# ME433_HW3_CPatino_schematic.net
KiCad netlist of a schematic drawn in EAGLE
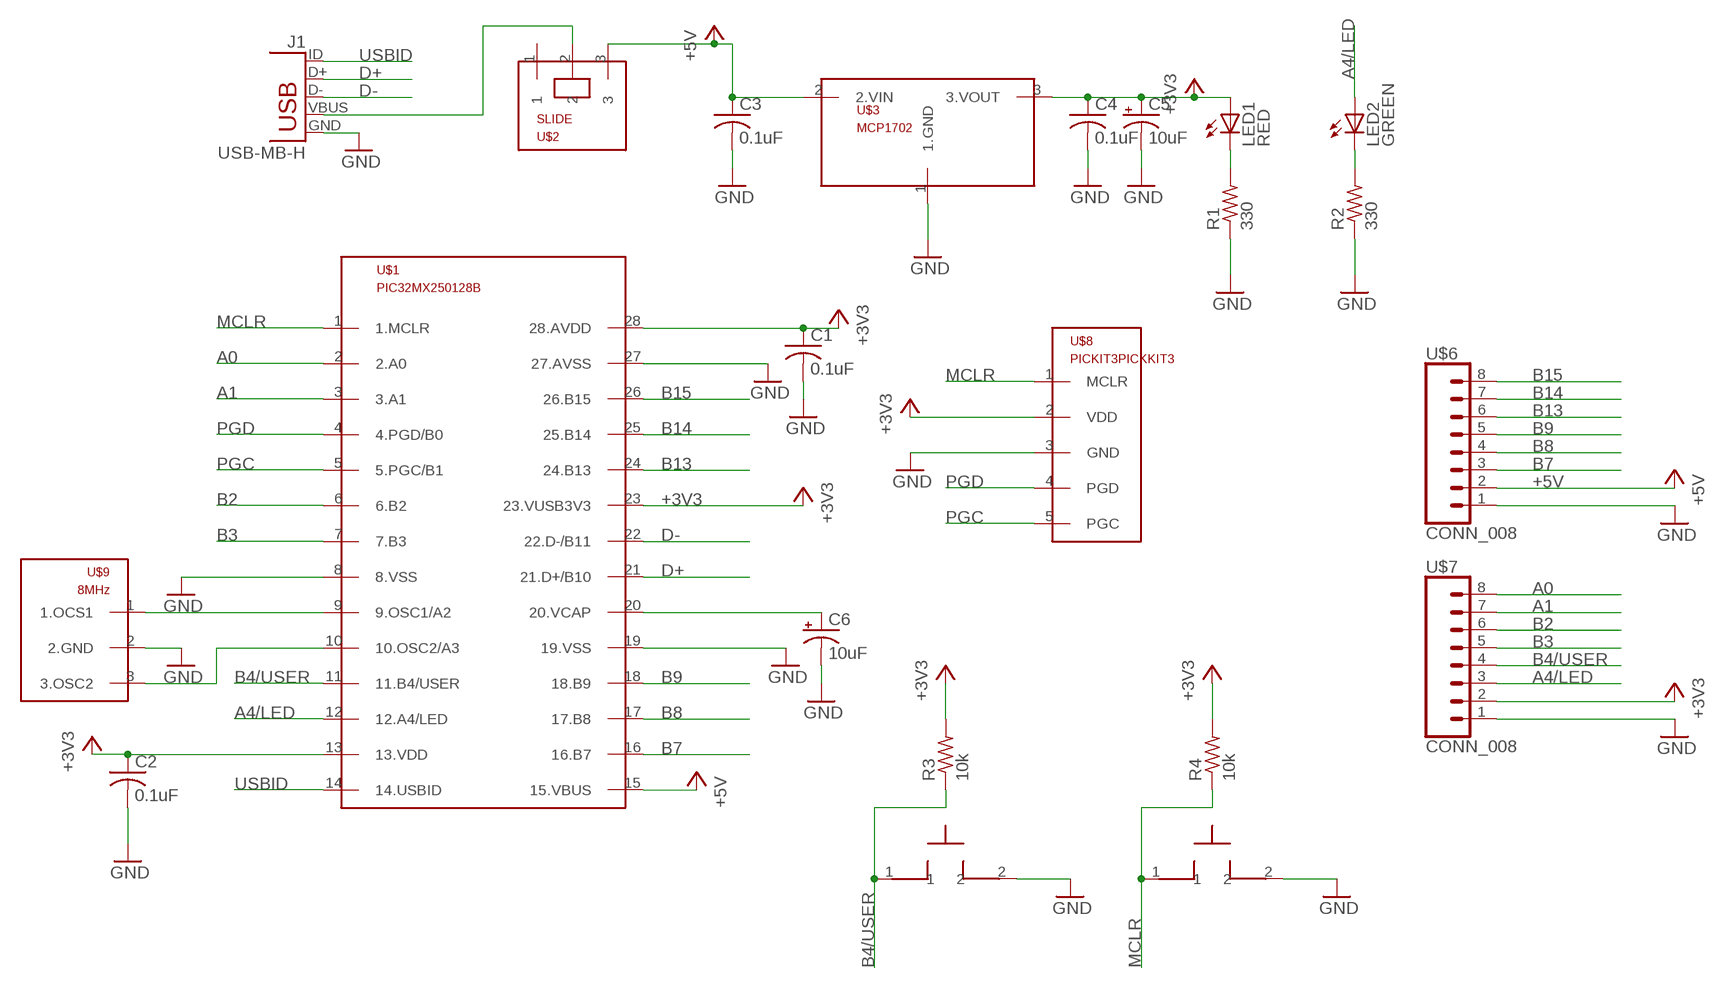
[diagram p0: schematic, sheet 1]

(export (version "E")
  (design (tool "Eeschema 10.0.6"))
  (components
    (comp (ref "C1")
      (value "0.1uF")
      (footprint "eagle-import:C025-025X050")
      (libsource (lib "eagle-import") (part "C-US025-025X050"))
    )
    (comp (ref "C2")
      (value "0.1uF")
      (footprint "eagle-import:C025-025X050")
      (libsource (lib "eagle-import") (part "C-US025-025X050"))
    )
    (comp (ref "C3")
      (value "0.1uF")
      (footprint "eagle-import:C025-025X050")
      (libsource (lib "eagle-import") (part "C-US025-025X050"))
    )
    (comp (ref "C4")
      (value "0.1uF")
      (footprint "eagle-import:C025-025X050")
      (libsource (lib "eagle-import") (part "C-US025-025X050"))
    )
    (comp (ref "C5")
      (value "10uF")
      (footprint "eagle-import:B45181B")
      (libsource (lib "eagle-import") (part "CPOL-USB45181B"))
    )
    (comp (ref "C6")
      (value "10uF")
      (footprint "eagle-import:B45181B")
      (libsource (lib "eagle-import") (part "CPOL-USB45181B"))
    )
    (comp (ref "J1")
      (value "USB-MB-H")
      (footprint "eagle-import:USB-MB-H")
      (libsource (lib "eagle-import") (part "USB-MB-H"))
    )
    (comp (ref "LED1")
      (value "RED")
      (footprint "eagle-import:LED3MM")
      (libsource (lib "eagle-import") (part "LED3MM"))
    )
    (comp (ref "LED2")
      (value "GREEN")
      (footprint "eagle-import:LED3MM")
      (libsource (lib "eagle-import") (part "LED3MM"))
    )
    (comp (ref "R1")
      (value "330")
      (footprint "eagle-import:0207_10")
      (libsource (lib "eagle-import") (part "R-US_0207/10"))
    )
    (comp (ref "R2")
      (value "330")
      (footprint "eagle-import:0207_10")
      (libsource (lib "eagle-import") (part "R-US_0207/10"))
    )
    (comp (ref "R3")
      (value "10k")
      (footprint "eagle-import:0207_10")
      (libsource (lib "eagle-import") (part "R-US_0207/10"))
    )
    (comp (ref "R4")
      (value "10k")
      (footprint "eagle-import:0207_10")
      (libsource (lib "eagle-import") (part "R-US_0207/10"))
    )
    (comp (ref "U$1")
      (value "PIC32MX250128B")
      (footprint "eagle-import:DIL28-3")
      (libsource (lib "eagle-import") (part "PIC32MX250128B"))
    )
    (comp (ref "U$2")
      (value "SLIDE")
      (footprint "eagle-import:SLIDE")
      (libsource (lib "eagle-import") (part "SLIDE"))
    )
    (comp (ref "U$3")
      (value "MCP1702")
      (footprint "eagle-import:TO92")
      (libsource (lib "eagle-import") (part "MCP1702"))
    )
    (comp (ref "U$4")
      (value "RESET")
      (footprint "eagle-import:PB")
      (libsource (lib "eagle-import") (part "PB"))
    )
    (comp (ref "U$5")
      (value "USER")
      (footprint "eagle-import:PB")
      (libsource (lib "eagle-import") (part "PB"))
    )
    (comp (ref "U$6")
      (value "CONN_008")
      (footprint "eagle-import:1X08")
      (libsource (lib "eagle-import") (part "CONN_008"))
    )
    (comp (ref "U$7")
      (value "CONN_008")
      (footprint "eagle-import:1X08")
      (libsource (lib "eagle-import") (part "CONN_008"))
    )
    (comp (ref "U$8")
      (value "PICKIT3PICKKIT3")
      (footprint "eagle-import:1X05")
      (libsource (lib "eagle-import") (part "PICKIT3PICKKIT3"))
    )
    (comp (ref "U$9")
      (value "8MHz")
      (footprint "eagle-import:OSC")
      (libsource (lib "eagle-import") (part "OSC"))
    )
  )
  (nets
    (net (code "1") (name "+3V3") (class "Default")
      (node (ref "C1") (pin "1") (pinfunction "1_1") (pintype "passive"))
      (node (ref "C2") (pin "1") (pinfunction "1_1") (pintype "passive"))
      (node (ref "C4") (pin "1") (pinfunction "1_1") (pintype "passive"))
      (node (ref "C5") (pin "+") (pinfunction "+_+") (pintype "passive"))
      (node (ref "LED1") (pin "A") (pinfunction "A_A") (pintype "passive"))
      (node (ref "R3") (pin "2") (pinfunction "2_2") (pintype "passive"))
      (node (ref "R4") (pin "2") (pinfunction "2_2") (pintype "passive"))
      (node (ref "U$1") (pin "13") (pinfunction "13.VDD_13") (pintype "bidirectional"))
      (node (ref "U$1") (pin "23") (pinfunction "23.VUSB3V3_23") (pintype "bidirectional"))
      (node (ref "U$1") (pin "28") (pinfunction "28.AVDD_28") (pintype "bidirectional"))
      (node (ref "U$3") (pin "3") (pinfunction "3.VOUT_3") (pintype "bidirectional"))
      (node (ref "U$7") (pin "2") (pinfunction "2_2") (pintype "passive"))
      (node (ref "U$8") (pin "2") (pinfunction "VDD_2") (pintype "bidirectional"))
    )
    (net (code "2") (name "+5V") (class "Default")
      (node (ref "C3") (pin "1") (pinfunction "1_1") (pintype "passive"))
      (node (ref "U$1") (pin "15") (pinfunction "15.VBUS_15") (pintype "bidirectional"))
      (node (ref "U$2") (pin "3") (pinfunction "3_3") (pintype "bidirectional"))
      (node (ref "U$3") (pin "2") (pinfunction "2.VIN_2") (pintype "bidirectional"))
      (node (ref "U$6") (pin "2") (pinfunction "2_2") (pintype "passive"))
    )
    (net (code "3") (name "/A0") (class "Default")
      (node (ref "U$1") (pin "2") (pinfunction "2.A0_2") (pintype "bidirectional"))
      (node (ref "U$7") (pin "8") (pinfunction "8_8") (pintype "passive"))
    )
    (net (code "4") (name "/A1") (class "Default")
      (node (ref "U$1") (pin "3") (pinfunction "3.A1_3") (pintype "bidirectional"))
      (node (ref "U$7") (pin "7") (pinfunction "7_7") (pintype "passive"))
    )
    (net (code "5") (name "/A4{slash}LED") (class "Default")
      (node (ref "LED2") (pin "A") (pinfunction "A_A") (pintype "passive"))
      (node (ref "U$1") (pin "12") (pinfunction "12.A4/LED_12") (pintype "bidirectional"))
      (node (ref "U$7") (pin "3") (pinfunction "3_3") (pintype "passive"))
    )
    (net (code "6") (name "/B2") (class "Default")
      (node (ref "U$1") (pin "6") (pinfunction "6.B2_6") (pintype "bidirectional"))
      (node (ref "U$7") (pin "6") (pinfunction "6_6") (pintype "passive"))
    )
    (net (code "7") (name "/B3") (class "Default")
      (node (ref "U$1") (pin "7") (pinfunction "7.B3_7") (pintype "bidirectional"))
      (node (ref "U$7") (pin "5") (pinfunction "5_5") (pintype "passive"))
    )
    (net (code "8") (name "/B4{slash}USER") (class "Default")
      (node (ref "R3") (pin "1") (pinfunction "1_1") (pintype "passive"))
      (node (ref "U$1") (pin "11") (pinfunction "11.B4/USER_11") (pintype "bidirectional"))
      (node (ref "U$4") (pin "1") (pinfunction "1_1") (pintype "bidirectional"))
      (node (ref "U$7") (pin "4") (pinfunction "4_4") (pintype "passive"))
    )
    (net (code "9") (name "/B7") (class "Default")
      (node (ref "U$1") (pin "16") (pinfunction "16.B7_16") (pintype "bidirectional"))
      (node (ref "U$6") (pin "3") (pinfunction "3_3") (pintype "passive"))
    )
    (net (code "10") (name "/B8") (class "Default")
      (node (ref "U$1") (pin "17") (pinfunction "17.B8_17") (pintype "bidirectional"))
      (node (ref "U$6") (pin "4") (pinfunction "4_4") (pintype "passive"))
    )
    (net (code "11") (name "/B9") (class "Default")
      (node (ref "U$1") (pin "18") (pinfunction "18.B9_18") (pintype "bidirectional"))
      (node (ref "U$6") (pin "5") (pinfunction "5_5") (pintype "passive"))
    )
    (net (code "12") (name "/B13") (class "Default")
      (node (ref "U$1") (pin "24") (pinfunction "24.B13_24") (pintype "bidirectional"))
      (node (ref "U$6") (pin "6") (pinfunction "6_6") (pintype "passive"))
    )
    (net (code "13") (name "/B14") (class "Default")
      (node (ref "U$1") (pin "25") (pinfunction "25.B14_25") (pintype "bidirectional"))
      (node (ref "U$6") (pin "7") (pinfunction "7_7") (pintype "passive"))
    )
    (net (code "14") (name "/B15") (class "Default")
      (node (ref "U$1") (pin "26") (pinfunction "26.B15_26") (pintype "bidirectional"))
      (node (ref "U$6") (pin "8") (pinfunction "8_8") (pintype "passive"))
    )
    (net (code "15") (name "/D+") (class "Default")
      (node (ref "J1") (pin "D+") (pinfunction "D+_D+") (pintype "bidirectional"))
      (node (ref "U$1") (pin "21") (pinfunction "21.D+/B10_21") (pintype "bidirectional"))
    )
    (net (code "16") (name "/D-") (class "Default")
      (node (ref "J1") (pin "D-") (pinfunction "D-_D-") (pintype "bidirectional"))
      (node (ref "U$1") (pin "22") (pinfunction "22.D-/B11_22") (pintype "bidirectional"))
    )
    (net (code "17") (name "/MCLR") (class "Default")
      (node (ref "R4") (pin "1") (pinfunction "1_1") (pintype "passive"))
      (node (ref "U$1") (pin "1") (pinfunction "1.MCLR_1") (pintype "bidirectional"))
      (node (ref "U$5") (pin "1") (pinfunction "1_1") (pintype "bidirectional"))
      (node (ref "U$8") (pin "1") (pinfunction "MCLR_1") (pintype "bidirectional"))
    )
    (net (code "18") (name "/PGC") (class "Default")
      (node (ref "U$1") (pin "5") (pinfunction "5.PGC/B1_5") (pintype "bidirectional"))
      (node (ref "U$8") (pin "5") (pinfunction "PGC_5") (pintype "bidirectional"))
    )
    (net (code "19") (name "/PGD") (class "Default")
      (node (ref "U$1") (pin "4") (pinfunction "4.PGD/B0_4") (pintype "bidirectional"))
      (node (ref "U$8") (pin "4") (pinfunction "PGD_4") (pintype "bidirectional"))
    )
    (net (code "20") (name "/USBID") (class "Default")
      (node (ref "J1") (pin "ID") (pinfunction "ID_ID") (pintype "bidirectional"))
      (node (ref "U$1") (pin "14") (pinfunction "14.USBID_14") (pintype "bidirectional"))
    )
    (net (code "21") (name "GND") (class "Default")
      (node (ref "C1") (pin "2") (pinfunction "2_2") (pintype "passive"))
      (node (ref "C2") (pin "2") (pinfunction "2_2") (pintype "passive"))
      (node (ref "C3") (pin "2") (pinfunction "2_2") (pintype "passive"))
      (node (ref "C4") (pin "2") (pinfunction "2_2") (pintype "passive"))
      (node (ref "C5") (pin "-") (pinfunction "-_-") (pintype "passive"))
      (node (ref "C6") (pin "-") (pinfunction "-_-") (pintype "passive"))
      (node (ref "J1") (pin "GND") (pinfunction "GND_GND") (pintype "bidirectional"))
      (node (ref "R1") (pin "1") (pinfunction "1_1") (pintype "passive"))
      (node (ref "R2") (pin "1") (pinfunction "1_1") (pintype "passive"))
      (node (ref "U$1") (pin "19") (pinfunction "19.VSS_19") (pintype "bidirectional"))
      (node (ref "U$1") (pin "27") (pinfunction "27.AVSS_27") (pintype "bidirectional"))
      (node (ref "U$1") (pin "8") (pinfunction "8.VSS_8") (pintype "bidirectional"))
      (node (ref "U$3") (pin "1") (pinfunction "1.GND_1") (pintype "bidirectional"))
      (node (ref "U$4") (pin "2") (pinfunction "2_2") (pintype "bidirectional"))
      (node (ref "U$5") (pin "2") (pinfunction "2_2") (pintype "bidirectional"))
      (node (ref "U$6") (pin "1") (pinfunction "1_1") (pintype "passive"))
      (node (ref "U$7") (pin "1") (pinfunction "1_1") (pintype "passive"))
      (node (ref "U$8") (pin "3") (pinfunction "GND_3") (pintype "bidirectional"))
      (node (ref "U$9") (pin "2") (pinfunction "2.GND_2") (pintype "bidirectional"))
    )
    (net (code "22") (name "Net-(J1-PadVBUS)") (class "Default")
      (node (ref "J1") (pin "VBUS") (pinfunction "VBUS_VBUS") (pintype "bidirectional"))
      (node (ref "U$2") (pin "2") (pinfunction "2_2") (pintype "bidirectional"))
    )
    (net (code "23") (name "Net-(LED1-C)") (class "Default")
      (node (ref "LED1") (pin "K") (pinfunction "C_K") (pintype "passive"))
      (node (ref "R1") (pin "2") (pinfunction "2_2") (pintype "passive"))
    )
    (net (code "24") (name "Net-(LED2-C)") (class "Default")
      (node (ref "LED2") (pin "K") (pinfunction "C_K") (pintype "passive"))
      (node (ref "R2") (pin "2") (pinfunction "2_2") (pintype "passive"))
    )
    (net (code "25") (name "Net-(U$1-9.OSC1{slash}A2)") (class "Default")
      (node (ref "U$1") (pin "9") (pinfunction "9.OSC1/A2_9") (pintype "bidirectional"))
      (node (ref "U$9") (pin "1") (pinfunction "1.OCS1_1") (pintype "bidirectional"))
    )
    (net (code "26") (name "Net-(U$1-10.OSC2{slash}A3)") (class "Default")
      (node (ref "U$1") (pin "10") (pinfunction "10.OSC2/A3_10") (pintype "bidirectional"))
      (node (ref "U$9") (pin "3") (pinfunction "3.OSC2_3") (pintype "bidirectional"))
    )
    (net (code "27") (name "Net-(U$1-20.VCAP)") (class "Default")
      (node (ref "C6") (pin "+") (pinfunction "+_+") (pintype "passive"))
      (node (ref "U$1") (pin "20") (pinfunction "20.VCAP_20") (pintype "bidirectional"))
    )
    (net (code "28") (name "unconnected-(U$2-Pad1)") (class "Default")
      (node (ref "U$2") (pin "1") (pinfunction "1_1") (pintype "bidirectional"))
    )
  )
)
